# Bistable_Clock.net
KiCad netlist of a schematic drawn in Altium Designer
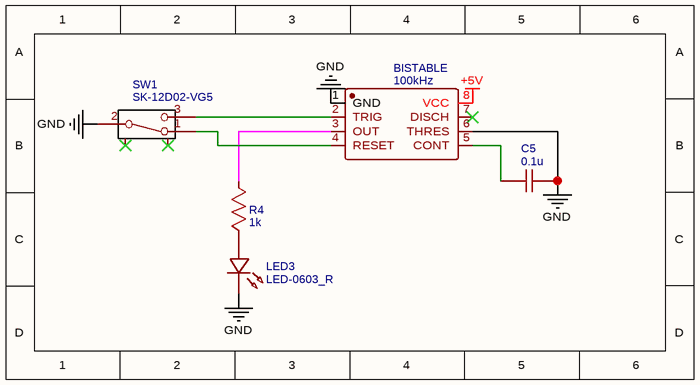
[diagram p0: Bistable Clock.schdoc]

(export (version "E")
  (design (tool "Eeschema 10.0.6"))
  (components
    (comp (ref "BISTABLE")
      (value "100kHz")
      (fields
        (field (name "MANUFACTURER") "TI(德州仪器)")
        (field (name "MANUFACTURER PART") "NE555PSRE4")
        (field (name "CONTRIBUTOR") "lcsc")
      )
      (libsource (lib "altium-import") (part "root_0_100kHz_"))
    )
    (comp (ref "C5")
      (value "0.1u")
      (fields (field (name "CONTRIBUTOR") "LCEDA_Lib"))
      (libsource (lib "altium-import") (part "root_0_0.1u_"))
    )
    (comp (ref "LED3")
      (value "LED-0603_R")
      (fields
        (field (name "MANUFACTURER") "EVERLIGHT(台湾亿光)")
        (field (name "MANUFACTURER PART") "19-217/R6C-AL1M2VY/3T")
        (field (name "CONTRIBUTOR") "LCEDA_01")
      )
      (libsource (lib "altium-import") (part "root_3_LED-0603_R_"))
    )
    (comp (ref "R4")
      (value "1k")
      (fields (field (name "CONTRIBUTOR") "LCEDA_Lib"))
      (libsource (lib "altium-import") (part "root_1_1k_"))
    )
    (comp (ref "SW1")
      (value "SK-12D02-VG5")
      (fields
        (field (name "MANUFACTURER") "Rectangular Connectors - Contacts")
        (field (name "CONTRIBUTOR") "LCSC")
      )
      (libsource (lib "altium-import") (part "root_0_SK-12D02-VG5_"))
    )
  )
  (nets
    (net (code "1") (name "+5V") (class "Default")
      (node (ref "BISTABLE") (pin "8") (pinfunction "VCC_8") (pintype "passive"))
    )
    (net (code "2") (name "GND") (class "Default")
      (node (ref "BISTABLE") (pin "1") (pinfunction "GND_1") (pintype "passive"))
      (node (ref "BISTABLE") (pin "6") (pinfunction "THRES_6") (pintype "passive"))
      (node (ref "C5") (pin "2") (pinfunction "2_2") (pintype "passive"))
      (node (ref "LED3") (pin "2") (pinfunction "2_2") (pintype "passive"))
      (node (ref "SW1") (pin "2") (pinfunction "2_2") (pintype "passive"))
    )
    (net (code "3") (name "Net-(BISTABLE-CONT)") (class "Default")
      (node (ref "BISTABLE") (pin "5") (pinfunction "CONT_5") (pintype "passive"))
      (node (ref "C5") (pin "1") (pinfunction "1_1") (pintype "passive"))
    )
    (net (code "4") (name "Net-(BISTABLE-OUT)") (class "Default")
      (node (ref "BISTABLE") (pin "3") (pinfunction "OUT_3") (pintype "passive"))
      (node (ref "R4") (pin "2") (pinfunction "2_2") (pintype "passive"))
    )
    (net (code "5") (name "Net-(BISTABLE-RESET)") (class "Default")
      (node (ref "BISTABLE") (pin "4") (pinfunction "RESET_4") (pintype "passive"))
      (node (ref "SW1") (pin "1") (pinfunction "1_1") (pintype "passive"))
    )
    (net (code "6") (name "Net-(BISTABLE-TRIG)") (class "Default")
      (node (ref "BISTABLE") (pin "2") (pinfunction "TRIG_2") (pintype "passive"))
      (node (ref "SW1") (pin "3") (pinfunction "3_3") (pintype "passive"))
    )
    (net (code "7") (name "Net-(LED3-Pad1)") (class "Default")
      (node (ref "LED3") (pin "1") (pinfunction "1_1") (pintype "passive"))
      (node (ref "R4") (pin "1") (pinfunction "1_1") (pintype "passive"))
    )
    (net (code "8") (name "unconnected-(BISTABLE-DISCH-Pad7)") (class "Default")
      (node (ref "BISTABLE") (pin "7") (pinfunction "DISCH_7") (pintype "passive+no_connect"))
    )
    (net (code "9") (name "unconnected-(SW1-Pad4)") (class "Default")
      (node (ref "SW1") (pin "4") (pinfunction "4_4") (pintype "passive+no_connect"))
    )
    (net (code "10") (name "unconnected-(SW1-Pad5)") (class "Default")
      (node (ref "SW1") (pin "5") (pinfunction "5_5") (pintype "passive+no_connect"))
    )
  )
)
